# PSU.net
KiCad netlist of a schematic drawn in Altium Designer
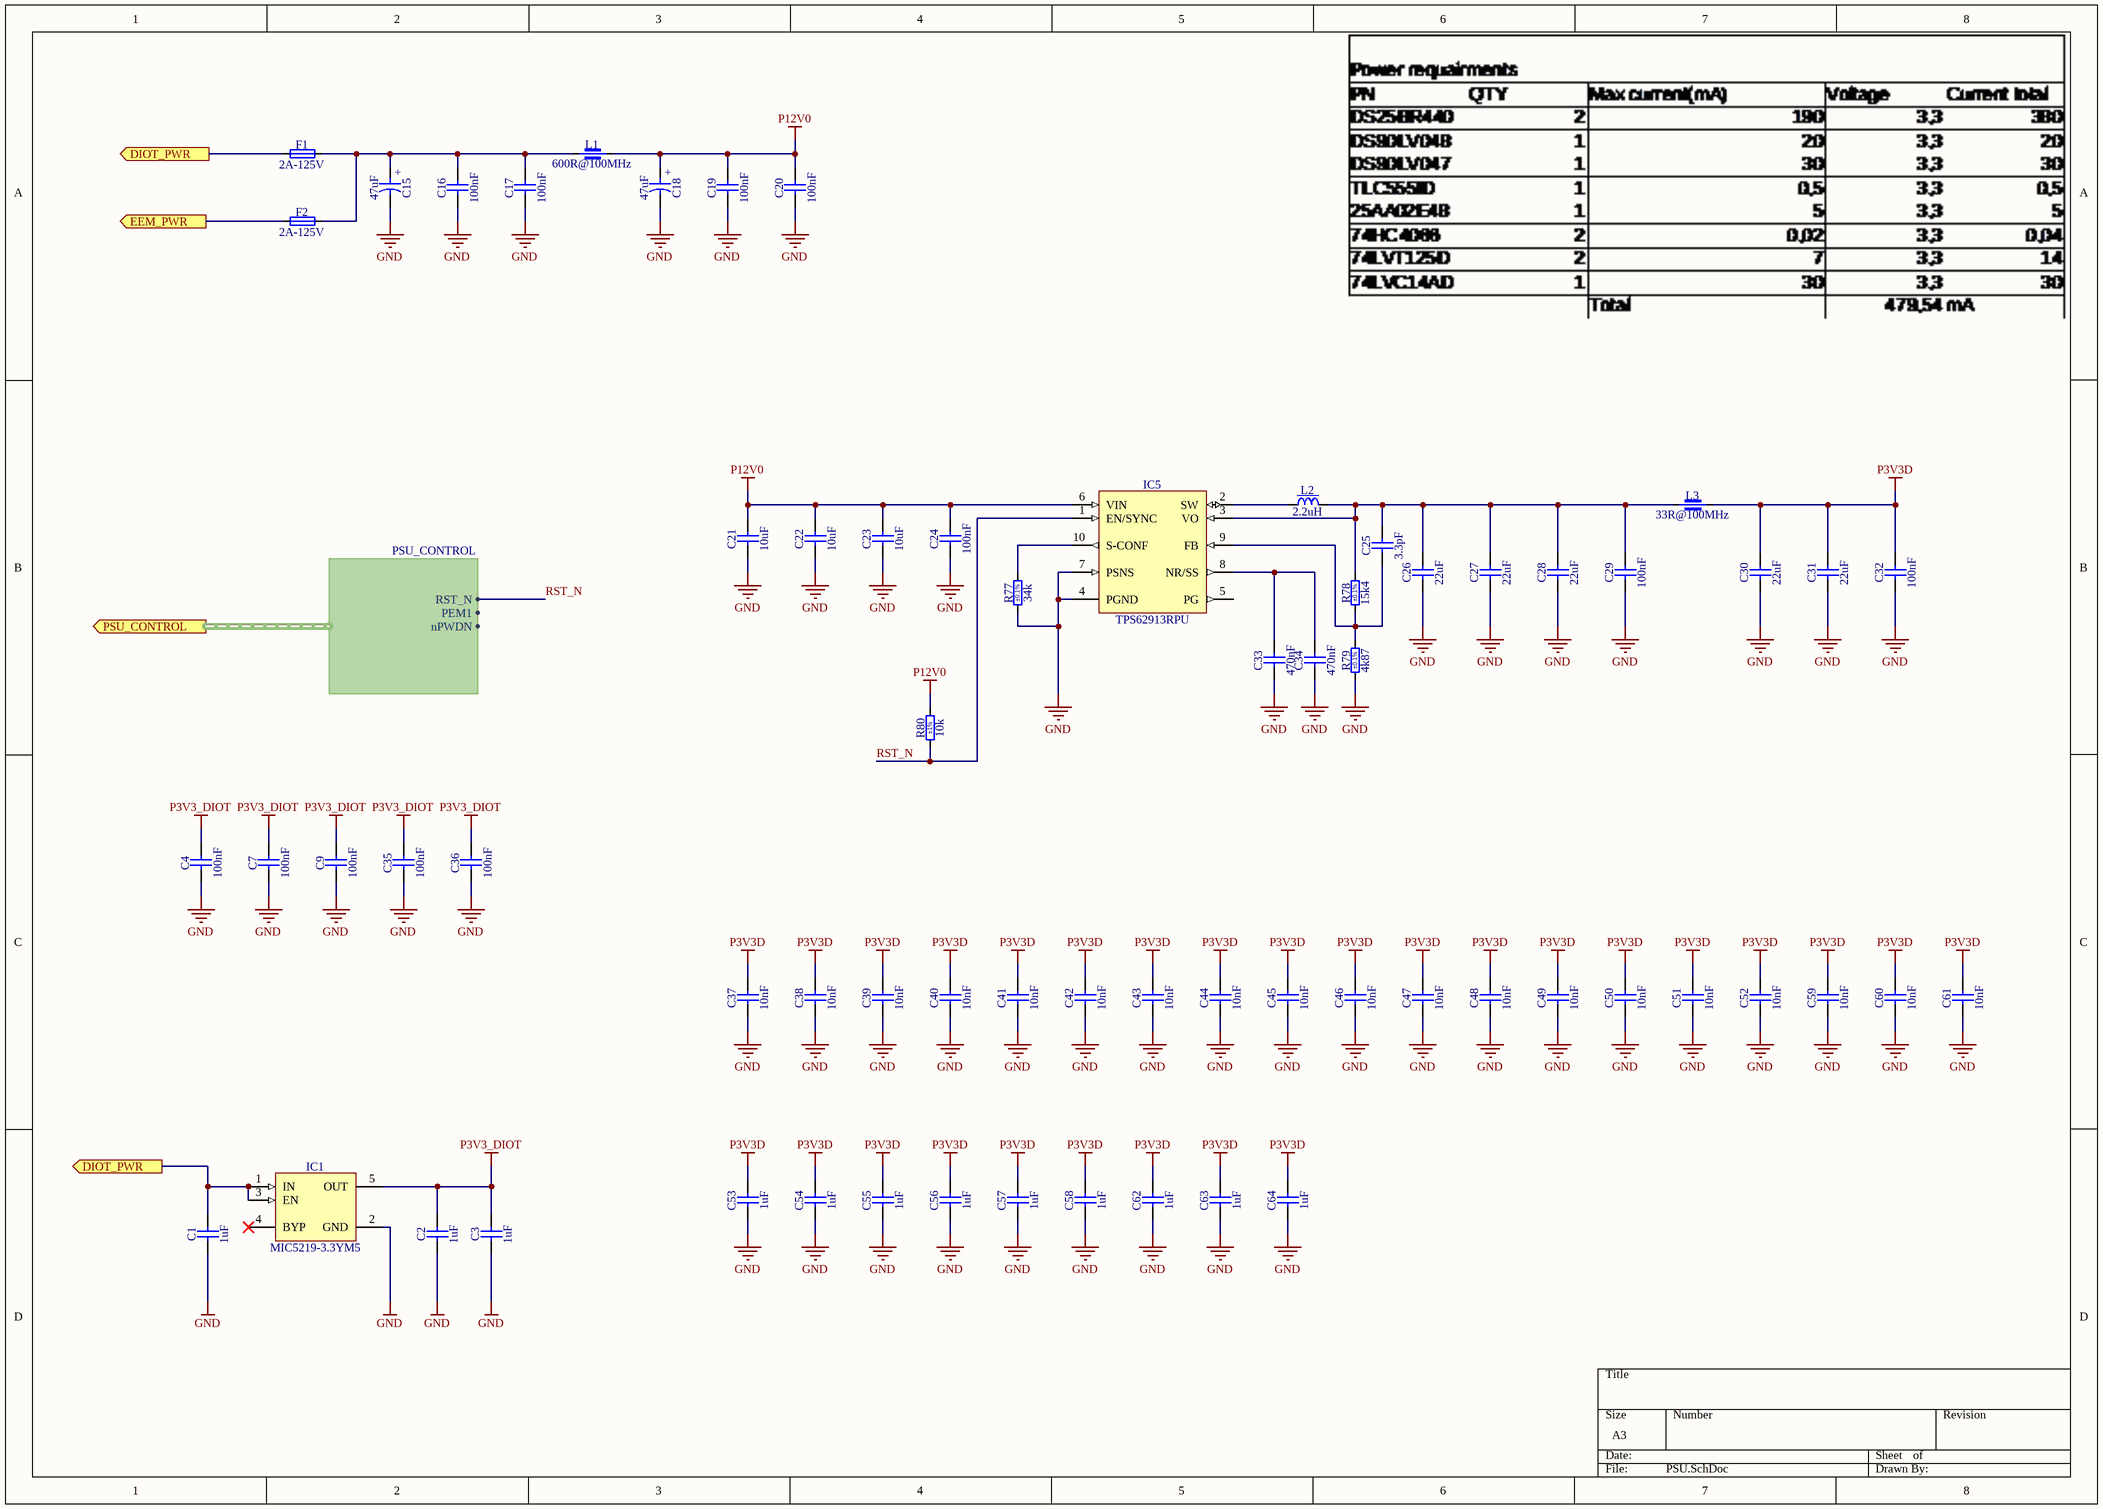
[diagram p0: PSU.SchDoc]

(export (version "E")
  (design (tool "Eeschema 10.0.6"))
  (components
    (comp (ref "C1")
      (value "1uF")
      (footprint "CAPC1608X87N")
      (description "Non-polarised capacitor")
      (fields
        (field (name "PART NUMBER") "CC0603_1UF_25V_10%_X7R")
        (field (name "VOLTAGE") "25V")
        (field (name "AUTHOR") "CERN DEM JLC")
      )
      (libsource (lib "Capacitors") (part "Capacitor - non polarized"))
    )
    (comp (ref "C2")
      (value "1uF")
      (footprint "CAPC1005X55N")
      (description "Non-polarised capacitor")
      (fields
        (field (name "PART NUMBER") "CC0402_1UF_16V_10%_X5R")
        (field (name "VOLTAGE") "16V")
        (field (name "AUTHOR") "CERN DEM JLC")
      )
      (libsource (lib "Capacitors") (part "Capacitor - non polarized"))
    )
    (comp (ref "C3")
      (value "1uF")
      (footprint "CAPC1005X55N")
      (description "Non-polarised capacitor")
      (fields
        (field (name "PART NUMBER") "CC0402_1UF_16V_10%_X5R")
        (field (name "VOLTAGE") "16V")
        (field (name "AUTHOR") "CERN DEM JLC")
      )
      (libsource (lib "Capacitors") (part "Capacitor - non polarized"))
    )
    (comp (ref "C4")
      (value "100nF")
      (footprint "CAPC1005X55N")
      (description "Non-polarised capacitor")
      (fields
        (field (name "PART NUMBER") "CC0402_100NF_16V_10%_X5R")
        (field (name "VOLTAGE") "16V")
        (field (name "AUTHOR") "CERN DEM JLC")
      )
      (libsource (lib "Capacitors") (part "Capacitor - non polarized"))
    )
    (comp (ref "C7")
      (value "100nF")
      (footprint "CAPC1005X55N")
      (description "Non-polarised capacitor")
      (fields
        (field (name "PART NUMBER") "CC0402_100NF_16V_10%_X5R")
        (field (name "VOLTAGE") "16V")
        (field (name "AUTHOR") "CERN DEM JLC")
      )
      (libsource (lib "Capacitors") (part "Capacitor - non polarized"))
    )
    (comp (ref "C9")
      (value "100nF")
      (footprint "CAPC1005X55N")
      (description "Non-polarised capacitor")
      (fields
        (field (name "PART NUMBER") "CC0402_100NF_16V_10%_X5R")
        (field (name "VOLTAGE") "16V")
        (field (name "AUTHOR") "CERN DEM JLC")
      )
      (libsource (lib "Capacitors") (part "Capacitor - non polarized"))
    )
    (comp (ref "C15")
      (value "47uF")
      (footprint "CAPMP7343X310N")
      (description "Polarised capacitor")
      (fields
        (field (name "PART NUMBER") "CTE7343-31_47UF_25V_10%")
        (field (name "VOLTAGE") "25V")
        (field (name "AUTHOR") "CERN DEM JLC")
      )
      (libsource (lib "Capacitors") (part "Capacitor - polarized"))
    )
    (comp (ref "C16")
      (value "100nF")
      (footprint "CAPC1608X90N")
      (description "Non-polarised capacitor")
      (fields
        (field (name "PART NUMBER") "CC0603_100NF_100V_10%_X7R")
        (field (name "VOLTAGE") "100V")
        (field (name "AUTHOR") "CERN DEM JLC")
      )
      (libsource (lib "Capacitors") (part "Capacitor - non polarized"))
    )
    (comp (ref "C17")
      (value "100nF")
      (footprint "CAPC1608X90N")
      (description "Non-polarised capacitor")
      (fields
        (field (name "PART NUMBER") "CC0603_100NF_100V_10%_X7R")
        (field (name "VOLTAGE") "100V")
        (field (name "AUTHOR") "CERN DEM JLC")
      )
      (libsource (lib "Capacitors") (part "Capacitor - non polarized"))
    )
    (comp (ref "C18")
      (value "47uF")
      (footprint "CAPMP7343X310N")
      (description "Polarised capacitor")
      (fields
        (field (name "PART NUMBER") "CTE7343-31_47UF_25V_10%")
        (field (name "VOLTAGE") "25V")
        (field (name "AUTHOR") "CERN DEM JLC")
      )
      (libsource (lib "Capacitors") (part "Capacitor - polarized"))
    )
    (comp (ref "C19")
      (value "100nF")
      (footprint "CAPC1608X90N")
      (description "Non-polarised capacitor")
      (fields
        (field (name "PART NUMBER") "CC0603_100NF_100V_10%_X7R")
        (field (name "VOLTAGE") "100V")
        (field (name "AUTHOR") "CERN DEM JLC")
      )
      (libsource (lib "Capacitors") (part "Capacitor - non polarized"))
    )
    (comp (ref "C20")
      (value "100nF")
      (footprint "CAPC1608X90N")
      (description "Non-polarised capacitor")
      (fields
        (field (name "PART NUMBER") "CC0603_100NF_100V_10%_X7R")
        (field (name "VOLTAGE") "100V")
        (field (name "AUTHOR") "CERN DEM JLC")
      )
      (libsource (lib "Capacitors") (part "Capacitor - non polarized"))
    )
    (comp (ref "C21")
      (value "10uF")
      (footprint "CAPC3216X180N")
      (description "Non-polarised capacitor")
      (fields
        (field (name "PART NUMBER") "CC1206_10UF_25V_10%_X7R")
        (field (name "VOLTAGE") "25V")
        (field (name "AUTHOR") "CERN DEM JLC")
      )
      (libsource (lib "Capacitors") (part "Capacitor - non polarized"))
    )
    (comp (ref "C22")
      (value "10uF")
      (footprint "CAPC3216X180N")
      (description "Non-polarised capacitor")
      (fields
        (field (name "PART NUMBER") "CC1206_10UF_25V_10%_X7R")
        (field (name "VOLTAGE") "25V")
        (field (name "AUTHOR") "CERN DEM JLC")
      )
      (libsource (lib "Capacitors") (part "Capacitor - non polarized"))
    )
    (comp (ref "C23")
      (value "10uF")
      (footprint "CAPC3216X180N")
      (description "Non-polarised capacitor")
      (fields
        (field (name "PART NUMBER") "CC1206_10UF_25V_10%_X7R")
        (field (name "VOLTAGE") "25V")
        (field (name "AUTHOR") "CERN DEM JLC")
      )
      (libsource (lib "Capacitors") (part "Capacitor - non polarized"))
    )
    (comp (ref "C24")
      (value "100nF")
      (footprint "CAPC2012X135N")
      (description "Non-polarised capacitor")
      (fields
        (field (name "PART NUMBER") "CC0805_100NF_50V_10%_X7R")
        (field (name "VOLTAGE") "50V")
        (field (name "AUTHOR") "CERN DEM JLC")
      )
      (libsource (lib "Capacitors") (part "Capacitor - non polarized"))
    )
    (comp (ref "C25")
      (value "3.3pF")
      (footprint "CAPC1608X87N")
      (description "Non-polarised capacitor")
      (fields
        (field (name "PART NUMBER") "CC0603_3.3PF_50V_0.25PF_NP0")
        (field (name "VOLTAGE") "50V")
        (field (name "AUTHOR") "CERN DEM JLC")
      )
      (libsource (lib "Capacitors") (part "Capacitor - non polarized"))
    )
    (comp (ref "C26")
      (value "22uF")
      (footprint "CAPC3216X180N")
      (description "Non-polarised capacitor")
      (fields
        (field (name "PART NUMBER") "CC1206_22UF_10V_10%_X7R")
        (field (name "VOLTAGE") "10V")
        (field (name "AUTHOR") "CERN DEM JLC")
      )
      (libsource (lib "Capacitors") (part "Capacitor - non polarized"))
    )
    (comp (ref "C27")
      (value "22uF")
      (footprint "CAPC3216X180N")
      (description "Non-polarised capacitor")
      (fields
        (field (name "PART NUMBER") "CC1206_22UF_10V_10%_X7R")
        (field (name "VOLTAGE") "10V")
        (field (name "AUTHOR") "CERN DEM JLC")
      )
      (libsource (lib "Capacitors") (part "Capacitor - non polarized"))
    )
    (comp (ref "C28")
      (value "22uF")
      (footprint "CAPC3216X180N")
      (description "Non-polarised capacitor")
      (fields
        (field (name "PART NUMBER") "CC1206_22UF_10V_10%_X7R")
        (field (name "VOLTAGE") "10V")
        (field (name "AUTHOR") "CERN DEM JLC")
      )
      (libsource (lib "Capacitors") (part "Capacitor - non polarized"))
    )
    (comp (ref "C29")
      (value "100nF")
      (footprint "CAPC3216X180N")
      (description "Non-polarised capacitor")
      (fields
        (field (name "PART NUMBER") "CC1206_100NF_50V_5%_C0G_TDK_CGA5L2C0G1H104J160AA")
        (field (name "VOLTAGE") "50V")
        (field (name "AUTHOR") "CERN DEM BC")
      )
      (libsource (lib "Capacitors") (part "Capacitor - non polarized"))
    )
    (comp (ref "C30")
      (value "22uF")
      (footprint "CAPC3216X180N")
      (description "Non-polarised capacitor")
      (fields
        (field (name "PART NUMBER") "CC1206_22UF_10V_10%_X7R")
        (field (name "VOLTAGE") "10V")
        (field (name "AUTHOR") "CERN DEM JLC")
      )
      (libsource (lib "Capacitors") (part "Capacitor - non polarized"))
    )
    (comp (ref "C31")
      (value "22uF")
      (footprint "CAPC3216X180N")
      (description "Non-polarised capacitor")
      (fields
        (field (name "PART NUMBER") "CC1206_22UF_10V_10%_X7R")
        (field (name "VOLTAGE") "10V")
        (field (name "AUTHOR") "CERN DEM JLC")
      )
      (libsource (lib "Capacitors") (part "Capacitor - non polarized"))
    )
    (comp (ref "C32")
      (value "100nF")
      (footprint "CAPC3216X180N")
      (description "Non-polarised capacitor")
      (fields
        (field (name "PART NUMBER") "CC1206_100NF_50V_5%_C0G_TDK_CGA5L2C0G1H104J160AA")
        (field (name "VOLTAGE") "50V")
        (field (name "AUTHOR") "CERN DEM BC")
      )
      (libsource (lib "Capacitors") (part "Capacitor - non polarized"))
    )
    (comp (ref "C33")
      (value "470nF")
      (footprint "CAPC1608X90N")
      (description "Non-polarised capacitor")
      (fields
        (field (name "PART NUMBER") "CC0603_470NF_16V_10%_X7R")
        (field (name "VOLTAGE") "16V")
        (field (name "AUTHOR") "CERN DEM BC")
      )
      (libsource (lib "Capacitors") (part "Capacitor - non polarized"))
    )
    (comp (ref "C34")
      (value "470nF")
      (footprint "CAPC1608X90N")
      (description "Non-polarised capacitor")
      (fields
        (field (name "PART NUMBER") "CC0603_470NF_16V_10%_X7R")
        (field (name "VOLTAGE") "16V")
        (field (name "AUTHOR") "CERN DEM BC")
      )
      (libsource (lib "Capacitors") (part "Capacitor - non polarized"))
    )
    (comp (ref "C35")
      (value "100nF")
      (footprint "CAPC1005X55N")
      (description "Non-polarised capacitor")
      (fields
        (field (name "PART NUMBER") "CC0402_100NF_16V_10%_X5R")
        (field (name "VOLTAGE") "16V")
        (field (name "AUTHOR") "CERN DEM JLC")
      )
      (libsource (lib "Capacitors") (part "Capacitor - non polarized"))
    )
    (comp (ref "C36")
      (value "100nF")
      (footprint "CAPC1005X55N")
      (description "Non-polarised capacitor")
      (fields
        (field (name "PART NUMBER") "CC0402_100NF_16V_10%_X5R")
        (field (name "VOLTAGE") "16V")
        (field (name "AUTHOR") "CERN DEM JLC")
      )
      (libsource (lib "Capacitors") (part "Capacitor - non polarized"))
    )
    (comp (ref "C37")
      (value "10nF")
      (footprint "CAPC1005X55N")
      (description "Non-polarised capacitor")
      (fields
        (field (name "PART NUMBER") "CC0402_10NF_16V_10%_X7R")
        (field (name "VOLTAGE") "16V")
        (field (name "AUTHOR") "CERN DEM JLC")
      )
      (libsource (lib "Capacitors") (part "Capacitor - non polarized"))
    )
    (comp (ref "C38")
      (value "10nF")
      (footprint "CAPC1005X55N")
      (description "Non-polarised capacitor")
      (fields
        (field (name "PART NUMBER") "CC0402_10NF_16V_10%_X7R")
        (field (name "VOLTAGE") "16V")
        (field (name "AUTHOR") "CERN DEM JLC")
      )
      (libsource (lib "Capacitors") (part "Capacitor - non polarized"))
    )
    (comp (ref "C39")
      (value "10nF")
      (footprint "CAPC1005X55N")
      (description "Non-polarised capacitor")
      (fields
        (field (name "PART NUMBER") "CC0402_10NF_16V_10%_X7R")
        (field (name "VOLTAGE") "16V")
        (field (name "AUTHOR") "CERN DEM JLC")
      )
      (libsource (lib "Capacitors") (part "Capacitor - non polarized"))
    )
    (comp (ref "C40")
      (value "10nF")
      (footprint "CAPC1005X55N")
      (description "Non-polarised capacitor")
      (fields
        (field (name "PART NUMBER") "CC0402_10NF_16V_10%_X7R")
        (field (name "VOLTAGE") "16V")
        (field (name "AUTHOR") "CERN DEM JLC")
      )
      (libsource (lib "Capacitors") (part "Capacitor - non polarized"))
    )
    (comp (ref "C41")
      (value "10nF")
      (footprint "CAPC1005X55N")
      (description "Non-polarised capacitor")
      (fields
        (field (name "PART NUMBER") "CC0402_10NF_16V_10%_X7R")
        (field (name "VOLTAGE") "16V")
        (field (name "AUTHOR") "CERN DEM JLC")
      )
      (libsource (lib "Capacitors") (part "Capacitor - non polarized"))
    )
    (comp (ref "C42")
      (value "10nF")
      (footprint "CAPC1005X55N")
      (description "Non-polarised capacitor")
      (fields
        (field (name "PART NUMBER") "CC0402_10NF_16V_10%_X7R")
        (field (name "VOLTAGE") "16V")
        (field (name "AUTHOR") "CERN DEM JLC")
      )
      (libsource (lib "Capacitors") (part "Capacitor - non polarized"))
    )
    (comp (ref "C43")
      (value "10nF")
      (footprint "CAPC1005X55N")
      (description "Non-polarised capacitor")
      (fields
        (field (name "PART NUMBER") "CC0402_10NF_16V_10%_X7R")
        (field (name "VOLTAGE") "16V")
        (field (name "AUTHOR") "CERN DEM JLC")
      )
      (libsource (lib "Capacitors") (part "Capacitor - non polarized"))
    )
    (comp (ref "C44")
      (value "10nF")
      (footprint "CAPC1005X55N")
      (description "Non-polarised capacitor")
      (fields
        (field (name "PART NUMBER") "CC0402_10NF_16V_10%_X7R")
        (field (name "VOLTAGE") "16V")
        (field (name "AUTHOR") "CERN DEM JLC")
      )
      (libsource (lib "Capacitors") (part "Capacitor - non polarized"))
    )
    (comp (ref "C45")
      (value "10nF")
      (footprint "CAPC1005X55N")
      (description "Non-polarised capacitor")
      (fields
        (field (name "PART NUMBER") "CC0402_10NF_16V_10%_X7R")
        (field (name "VOLTAGE") "16V")
        (field (name "AUTHOR") "CERN DEM JLC")
      )
      (libsource (lib "Capacitors") (part "Capacitor - non polarized"))
    )
    (comp (ref "C46")
      (value "10nF")
      (footprint "CAPC1005X55N")
      (description "Non-polarised capacitor")
      (fields
        (field (name "PART NUMBER") "CC0402_10NF_16V_10%_X7R")
        (field (name "VOLTAGE") "16V")
        (field (name "AUTHOR") "CERN DEM JLC")
      )
      (libsource (lib "Capacitors") (part "Capacitor - non polarized"))
    )
    (comp (ref "C47")
      (value "10nF")
      (footprint "CAPC1005X55N")
      (description "Non-polarised capacitor")
      (fields
        (field (name "PART NUMBER") "CC0402_10NF_16V_10%_X7R")
        (field (name "VOLTAGE") "16V")
        (field (name "AUTHOR") "CERN DEM JLC")
      )
      (libsource (lib "Capacitors") (part "Capacitor - non polarized"))
    )
    (comp (ref "C48")
      (value "10nF")
      (footprint "CAPC1005X55N")
      (description "Non-polarised capacitor")
      (fields
        (field (name "PART NUMBER") "CC0402_10NF_16V_10%_X7R")
        (field (name "VOLTAGE") "16V")
        (field (name "AUTHOR") "CERN DEM JLC")
      )
      (libsource (lib "Capacitors") (part "Capacitor - non polarized"))
    )
    (comp (ref "C49")
      (value "10nF")
      (footprint "CAPC1005X55N")
      (description "Non-polarised capacitor")
      (fields
        (field (name "PART NUMBER") "CC0402_10NF_16V_10%_X7R")
        (field (name "VOLTAGE") "16V")
        (field (name "AUTHOR") "CERN DEM JLC")
      )
      (libsource (lib "Capacitors") (part "Capacitor - non polarized"))
    )
    (comp (ref "C50")
      (value "10nF")
      (footprint "CAPC1005X55N")
      (description "Non-polarised capacitor")
      (fields
        (field (name "PART NUMBER") "CC0402_10NF_16V_10%_X7R")
        (field (name "VOLTAGE") "16V")
        (field (name "AUTHOR") "CERN DEM JLC")
      )
      (libsource (lib "Capacitors") (part "Capacitor - non polarized"))
    )
    (comp (ref "C51")
      (value "10nF")
      (footprint "CAPC1005X55N")
      (description "Non-polarised capacitor")
      (fields
        (field (name "PART NUMBER") "CC0402_10NF_16V_10%_X7R")
        (field (name "VOLTAGE") "16V")
        (field (name "AUTHOR") "CERN DEM JLC")
      )
      (libsource (lib "Capacitors") (part "Capacitor - non polarized"))
    )
    (comp (ref "C52")
      (value "10nF")
      (footprint "CAPC1005X55N")
      (description "Non-polarised capacitor")
      (fields
        (field (name "PART NUMBER") "CC0402_10NF_16V_10%_X7R")
        (field (name "VOLTAGE") "16V")
        (field (name "AUTHOR") "CERN DEM JLC")
      )
      (libsource (lib "Capacitors") (part "Capacitor - non polarized"))
    )
    (comp (ref "C53")
      (value "1uF")
      (footprint "CAPC2012X135N")
      (description "Non-polarised capacitor")
      (fields
        (field (name "PART NUMBER") "CC0805_1UF_16V_10%_X7R")
        (field (name "VOLTAGE") "16V")
        (field (name "AUTHOR") "CERN DEM JLC")
      )
      (libsource (lib "Capacitors") (part "Capacitor - non polarized"))
    )
    (comp (ref "C54")
      (value "1uF")
      (footprint "CAPC2012X135N")
      (description "Non-polarised capacitor")
      (fields
        (field (name "PART NUMBER") "CC0805_1UF_16V_10%_X7R")
        (field (name "VOLTAGE") "16V")
        (field (name "AUTHOR") "CERN DEM JLC")
      )
      (libsource (lib "Capacitors") (part "Capacitor - non polarized"))
    )
    (comp (ref "C55")
      (value "1uF")
      (footprint "CAPC2012X135N")
      (description "Non-polarised capacitor")
      (fields
        (field (name "PART NUMBER") "CC0805_1UF_16V_10%_X7R")
        (field (name "VOLTAGE") "16V")
        (field (name "AUTHOR") "CERN DEM JLC")
      )
      (libsource (lib "Capacitors") (part "Capacitor - non polarized"))
    )
    (comp (ref "C56")
      (value "1uF")
      (footprint "CAPC2012X135N")
      (description "Non-polarised capacitor")
      (fields
        (field (name "PART NUMBER") "CC0805_1UF_16V_10%_X7R")
        (field (name "VOLTAGE") "16V")
        (field (name "AUTHOR") "CERN DEM JLC")
      )
      (libsource (lib "Capacitors") (part "Capacitor - non polarized"))
    )
    (comp (ref "C57")
      (value "1uF")
      (footprint "CAPC2012X135N")
      (description "Non-polarised capacitor")
      (fields
        (field (name "PART NUMBER") "CC0805_1UF_16V_10%_X7R")
        (field (name "VOLTAGE") "16V")
        (field (name "AUTHOR") "CERN DEM JLC")
      )
      (libsource (lib "Capacitors") (part "Capacitor - non polarized"))
    )
    (comp (ref "C58")
      (value "1uF")
      (footprint "CAPC2012X135N")
      (description "Non-polarised capacitor")
      (fields
        (field (name "PART NUMBER") "CC0805_1UF_16V_10%_X7R")
        (field (name "VOLTAGE") "16V")
        (field (name "AUTHOR") "CERN DEM JLC")
      )
      (libsource (lib "Capacitors") (part "Capacitor - non polarized"))
    )
    (comp (ref "C59")
      (value "10nF")
      (footprint "CAPC1005X55N")
      (description "Non-polarised capacitor")
      (fields
        (field (name "PART NUMBER") "CC0402_10NF_16V_10%_X7R")
        (field (name "VOLTAGE") "16V")
        (field (name "AUTHOR") "CERN DEM JLC")
      )
      (libsource (lib "Capacitors") (part "Capacitor - non polarized"))
    )
    (comp (ref "C60")
      (value "10nF")
      (footprint "CAPC1005X55N")
      (description "Non-polarised capacitor")
      (fields
        (field (name "PART NUMBER") "CC0402_10NF_16V_10%_X7R")
        (field (name "VOLTAGE") "16V")
        (field (name "AUTHOR") "CERN DEM JLC")
      )
      (libsource (lib "Capacitors") (part "Capacitor - non polarized"))
    )
    (comp (ref "C61")
      (value "10nF")
      (footprint "CAPC1005X55N")
      (description "Non-polarised capacitor")
      (fields
        (field (name "PART NUMBER") "CC0402_10NF_16V_10%_X7R")
        (field (name "VOLTAGE") "16V")
        (field (name "AUTHOR") "CERN DEM JLC")
      )
      (libsource (lib "Capacitors") (part "Capacitor - non polarized"))
    )
    (comp (ref "C62")
      (value "1uF")
      (footprint "CAPC2012X135N")
      (description "Non-polarised capacitor")
      (fields
        (field (name "PART NUMBER") "CC0805_1UF_16V_10%_X7R")
        (field (name "VOLTAGE") "16V")
        (field (name "AUTHOR") "CERN DEM JLC")
      )
      (libsource (lib "Capacitors") (part "Capacitor - non polarized"))
    )
    (comp (ref "C63")
      (value "1uF")
      (footprint "CAPC2012X135N")
      (description "Non-polarised capacitor")
      (fields
        (field (name "PART NUMBER") "CC0805_1UF_16V_10%_X7R")
        (field (name "VOLTAGE") "16V")
        (field (name "AUTHOR") "CERN DEM JLC")
      )
      (libsource (lib "Capacitors") (part "Capacitor - non polarized"))
    )
    (comp (ref "C64")
      (value "1uF")
      (footprint "CAPC2012X135N")
      (description "Non-polarised capacitor")
      (fields
        (field (name "PART NUMBER") "CC0805_1UF_16V_10%_X7R")
        (field (name "VOLTAGE") "16V")
        (field (name "AUTHOR") "CERN DEM JLC")
      )
      (libsource (lib "Capacitors") (part "Capacitor - non polarized"))
    )
    (comp (ref "F1")
      (value "2A-125V")
      (footprint "FUSE_LITTELFUSE_0154")
      (description "Fuse")
      (fields
        (field (name "PART NUMBER") "FUSE_LITTELFUSE_0154002.DR")
        (field (name "MANUFACTURER") "LITTELFUSE")
        (field (name "AUTHOR") "CERN DEM JMW")
      )
      (libsource (lib "Eletro-mechanical") (part "Fuse"))
    )
    (comp (ref "F2")
      (value "2A-125V")
      (footprint "FUSE_LITTELFUSE_0154")
      (description "Fuse")
      (fields
        (field (name "PART NUMBER") "FUSE_LITTELFUSE_0154002.DR")
        (field (name "MANUFACTURER") "LITTELFUSE")
        (field (name "AUTHOR") "CERN DEM JMW")
      )
      (libsource (lib "Eletro-mechanical") (part "Fuse"))
    )
    (comp (ref "IC1")
      (value "MIC5219-3.3YM5")
      (footprint "SOT95P280X145-5N")
      (description "500mA Peak Output LDO Regulator")
      (fields (field (name "MANUFACTURER") "MICROCHIP TECHNOLOGY") (field (name "AUTHOR") "CERN DEM WB"))
      (libsource (lib "ICs And Semiconductors") (part "MIC5219-X.XYM5"))
    )
    (comp (ref "IC5")
      (value "TPS62913RPU")
      (footprint "TEXAS_RPU0010A")
      (fields (field (name "MANUFACTURER") "TEXAS INSTRUMENTS") (field (name "AUTHOR") "CERN DEM BC"))
      (libsource (lib "ICs And Semiconductors") (part "TPS6291x"))
    )
    (comp (ref "L1")
      (value "600R@100MHz")
      (footprint "INDC2012X110N")
      (fields
        (field (name "PART NUMBER") "IND0805_WURTH_742792040")
        (field (name "POWER") "2A")
        (field (name "TOLERANCE") "±25%")
        (field (name "AUTHOR") "CERN DEM JLC")
      )
      (libsource (lib "Inductors & Transformers") (part "Ferrite Bead"))
    )
    (comp (ref "L2")
      (value "2.2uH")
      (footprint "IND_WURTH_WE-MAPI_4020")
      (description "Inductor With Core")
      (fields
        (field (name "PART NUMBER") "IND_2.2UH_20%_WURTH_WE-MAPI-74438356022")
        (field (name "POWER") "4.7A")
        (field (name "AUTHOR") "CERN DEM HF")
      )
      (libsource (lib "Inductors & Transformers") (part "Inductor With Magnetic core"))
    )
    (comp (ref "L3")
      (value "33R@100MHz")
      (footprint "IND_KEMET_Z0805PWS")
      (fields
        (field (name "PART NUMBER") "IND0805_KEMET_Z0805C330BPWS")
        (field (name "POWER") "4A")
        (field (name "TOLERANCE") "±25%")
        (field (name "AUTHOR") "CERN DEM JMW")
      )
      (libsource (lib "Inductors & Transformers") (part "Ferrite Bead"))
    )
    (comp (ref "R77")
      (value "34k")
      (footprint "RESC1608X55N")
      (description "Resistor - 0.1%")
      (fields
        (field (name "TOLERANCE") "±0.1%")
        (field (name "PART NUMBER") "R0603_34K_0.1%_0.063W_10PPM")
        (field (name "POWER") "0.063W")
        (field (name "AUTHOR") "CERN DEM JLC")
      )
      (libsource (lib "Resistors") (part "Resistor - 0.1%"))
    )
    (comp (ref "R78")
      (value "15k4")
      (footprint "RESC1608X55N")
      (description "Resistor - 0.1%")
      (fields
        (field (name "TOLERANCE") "±0.1%")
        (field (name "PART NUMBER") "R0603_15K4_0.1%_0.063W_10PPM")
        (field (name "POWER") "0.063W")
        (field (name "AUTHOR") "CERN DEM JLC")
      )
      (libsource (lib "Resistors") (part "Resistor - 0.1%"))
    )
    (comp (ref "R79")
      (value "4k87")
      (footprint "RESC1608X55N")
      (description "Resistor - 0.1%")
      (fields
        (field (name "TOLERANCE") "±0.1%")
        (field (name "PART NUMBER") "R0603_4K87_0.1%_0.063W_10PPM")
        (field (name "POWER") "0.063W")
        (field (name "AUTHOR") "CERN DEM JLC")
      )
      (libsource (lib "Resistors") (part "Resistor - 0.1%"))
    )
    (comp (ref "R80")
      (value "10k")
      (footprint "RESC1608X55N")
      (description "Resistor - 1%")
      (fields
        (field (name "TOLERANCE") "±1%")
        (field (name "PART NUMBER") "R0603_10K_1%_0.1W_100PPM")
        (field (name "POWER") "0.1W")
        (field (name "AUTHOR") "CERN DEM JLC")
      )
      (libsource (lib "Resistors") (part "Resistor - 1%"))
    )
  )
  (nets
    (net (code "2") (name "/DIOT_PWR") (class "Default")
      (node (ref "C1") (pin "2") (pinfunction "2_2") (pintype "passive"))
      (node (ref "F1") (pin "1") (pinfunction "1_1") (pintype "passive"))
      (node (ref "IC1") (pin "1") (pinfunction "IN_1") (pintype "input"))
      (node (ref "IC1") (pin "3") (pinfunction "EN_3") (pintype "input"))
    )
    (net (code "3") (name "/EEM_PWR") (class "Default")
      (node (ref "F2") (pin "1") (pinfunction "1_1") (pintype "passive"))
    )
    (net (code "4") (name "/RST_N") (class "Default")
      (node (ref "IC5") (pin "1") (pinfunction "EN/SYNC_1") (pintype "input"))
      (node (ref "R80") (pin "1") (pinfunction "1_1") (pintype "passive"))
    )
    (net (code "6") (name "GND") (class "Default")
      (node (ref "C1") (pin "1") (pinfunction "1_1") (pintype "passive"))
      (node (ref "C15") (pin "2") (pinfunction "2_2") (pintype "passive"))
      (node (ref "C16") (pin "1") (pinfunction "1_1") (pintype "passive"))
      (node (ref "C17") (pin "1") (pinfunction "1_1") (pintype "passive"))
      (node (ref "C18") (pin "2") (pinfunction "2_2") (pintype "passive"))
      (node (ref "C19") (pin "1") (pinfunction "1_1") (pintype "passive"))
      (node (ref "C2") (pin "1") (pinfunction "1_1") (pintype "passive"))
      (node (ref "C20") (pin "1") (pinfunction "1_1") (pintype "passive"))
      (node (ref "C21") (pin "1") (pinfunction "1_1") (pintype "passive"))
      (node (ref "C22") (pin "1") (pinfunction "1_1") (pintype "passive"))
      (node (ref "C23") (pin "1") (pinfunction "1_1") (pintype "passive"))
      (node (ref "C24") (pin "1") (pinfunction "1_1") (pintype "passive"))
      (node (ref "C26") (pin "1") (pinfunction "1_1") (pintype "passive"))
      (node (ref "C27") (pin "1") (pinfunction "1_1") (pintype "passive"))
      (node (ref "C28") (pin "1") (pinfunction "1_1") (pintype "passive"))
      (node (ref "C29") (pin "1") (pinfunction "1_1") (pintype "passive"))
      (node (ref "C3") (pin "1") (pinfunction "1_1") (pintype "passive"))
      (node (ref "C30") (pin "1") (pinfunction "1_1") (pintype "passive"))
      (node (ref "C31") (pin "1") (pinfunction "1_1") (pintype "passive"))
      (node (ref "C32") (pin "1") (pinfunction "1_1") (pintype "passive"))
      (node (ref "C33") (pin "1") (pinfunction "1_1") (pintype "passive"))
      (node (ref "C34") (pin "1") (pinfunction "1_1") (pintype "passive"))
      (node (ref "C35") (pin "1") (pinfunction "1_1") (pintype "passive"))
      (node (ref "C36") (pin "1") (pinfunction "1_1") (pintype "passive"))
      (node (ref "C37") (pin "1") (pinfunction "1_1") (pintype "passive"))
      (node (ref "C38") (pin "1") (pinfunction "1_1") (pintype "passive"))
      (node (ref "C39") (pin "1") (pinfunction "1_1") (pintype "passive"))
      (node (ref "C4") (pin "1") (pinfunction "1_1") (pintype "passive"))
      (node (ref "C40") (pin "1") (pinfunction "1_1") (pintype "passive"))
      (node (ref "C41") (pin "1") (pinfunction "1_1") (pintype "passive"))
      (node (ref "C42") (pin "1") (pinfunction "1_1") (pintype "passive"))
      (node (ref "C43") (pin "1") (pinfunction "1_1") (pintype "passive"))
      (node (ref "C44") (pin "1") (pinfunction "1_1") (pintype "passive"))
      (node (ref "C45") (pin "1") (pinfunction "1_1") (pintype "passive"))
      (node (ref "C46") (pin "1") (pinfunction "1_1") (pintype "passive"))
      (node (ref "C47") (pin "1") (pinfunction "1_1") (pintype "passive"))
      (node (ref "C48") (pin "1") (pinfunction "1_1") (pintype "passive"))
      (node (ref "C49") (pin "1") (pinfunction "1_1") (pintype "passive"))
      (node (ref "C50") (pin "1") (pinfunction "1_1") (pintype "passive"))
      (node (ref "C51") (pin "1") (pinfunction "1_1") (pintype "passive"))
      (node (ref "C52") (pin "1") (pinfunction "1_1") (pintype "passive"))
      (node (ref "C53") (pin "1") (pinfunction "1_1") (pintype "passive"))
      (node (ref "C54") (pin "1") (pinfunction "1_1") (pintype "passive"))
      (node (ref "C55") (pin "1") (pinfunction "1_1") (pintype "passive"))
      (node (ref "C56") (pin "1") (pinfunction "1_1") (pintype "passive"))
      (node (ref "C57") (pin "1") (pinfunction "1_1") (pintype "passive"))
      (node (ref "C58") (pin "1") (pinfunction "1_1") (pintype "passive"))
      (node (ref "C59") (pin "1") (pinfunction "1_1") (pintype "passive"))
      (node (ref "C60") (pin "1") (pinfunction "1_1") (pintype "passive"))
      (node (ref "C61") (pin "1") (pinfunction "1_1") (pintype "passive"))
      (node (ref "C62") (pin "1") (pinfunction "1_1") (pintype "passive"))
      (node (ref "C63") (pin "1") (pinfunction "1_1") (pintype "passive"))
      (node (ref "C64") (pin "1") (pinfunction "1_1") (pintype "passive"))
      (node (ref "C7") (pin "1") (pinfunction "1_1") (pintype "passive"))
      (node (ref "C9") (pin "1") (pinfunction "1_1") (pintype "passive"))
      (node (ref "IC1") (pin "2") (pinfunction "GND_2") (pintype "power_in"))
      (node (ref "IC5") (pin "4") (pinfunction "PGND_4") (pintype "power_in"))
      (node (ref "IC5") (pin "7") (pinfunction "PSNS_7") (pintype "input"))
      (node (ref "R77") (pin "1") (pinfunction "1_1") (pintype "passive"))
      (node (ref "R79") (pin "1") (pinfunction "1_1") (pintype "passive"))
    )
    (net (code "7") (name "Net-(C15-Pad1)") (class "Default")
      (node (ref "C15") (pin "1") (pinfunction "1_1") (pintype "passive"))
      (node (ref "C16") (pin "2") (pinfunction "2_2") (pintype "passive"))
      (node (ref "C17") (pin "2") (pinfunction "2_2") (pintype "passive"))
      (node (ref "F1") (pin "2") (pinfunction "2_2") (pintype "passive"))
      (node (ref "F2") (pin "2") (pinfunction "2_2") (pintype "passive"))
      (node (ref "L1") (pin "1") (pinfunction "1_1") (pintype "passive"))
    )
    (net (code "8") (name "Net-(IC5-FB)") (class "Default")
      (node (ref "C25") (pin "1") (pinfunction "1_1") (pintype "passive"))
      (node (ref "IC5") (pin "9") (pinfunction "FB_9") (pintype "input"))
      (node (ref "R78") (pin "1") (pinfunction "1_1") (pintype "passive"))
      (node (ref "R79") (pin "2") (pinfunction "2_2") (pintype "passive"))
    )
    (net (code "9") (name "Net-(IC5-NR{slash}SS)") (class "Default")
      (node (ref "C33") (pin "2") (pinfunction "2_2") (pintype "passive"))
      (node (ref "C34") (pin "2") (pinfunction "2_2") (pintype "passive"))
      (node (ref "IC5") (pin "8") (pinfunction "NR/SS_8") (pintype "output"))
    )
    (net (code "10") (name "Net-(IC5-S-CONF)") (class "Default")
      (node (ref "IC5") (pin "10") (pinfunction "S-CONF_10") (pintype "output"))
      (node (ref "R77") (pin "2") (pinfunction "2_2") (pintype "passive"))
    )
    (net (code "11") (name "Net-(IC5-SW)") (class "Default")
      (node (ref "IC5") (pin "2") (pinfunction "SW_2") (pintype "bidirectional"))
      (node (ref "L2") (pin "1") (pinfunction "1_1") (pintype "passive"))
    )
    (net (code "12") (name "Net-(IC5-VO)") (class "Default")
      (node (ref "C25") (pin "2") (pinfunction "2_2") (pintype "passive"))
      (node (ref "C26") (pin "2") (pinfunction "2_2") (pintype "passive"))
      (node (ref "C27") (pin "2") (pinfunction "2_2") (pintype "passive"))
      (node (ref "C28") (pin "2") (pinfunction "2_2") (pintype "passive"))
      (node (ref "C29") (pin "2") (pinfunction "2_2") (pintype "passive"))
      (node (ref "IC5") (pin "3") (pinfunction "VO_3") (pintype "input"))
      (node (ref "L2") (pin "2") (pinfunction "2_2") (pintype "passive"))
      (node (ref "L3") (pin "1") (pinfunction "1_1") (pintype "passive"))
      (node (ref "R78") (pin "2") (pinfunction "2_2") (pintype "passive"))
    )
    (net (code "13") (name "P3V3D") (class "Default")
      (node (ref "C30") (pin "2") (pinfunction "2_2") (pintype "passive"))
      (node (ref "C31") (pin "2") (pinfunction "2_2") (pintype "passive"))
      (node (ref "C32") (pin "2") (pinfunction "2_2") (pintype "passive"))
      (node (ref "C37") (pin "2") (pinfunction "2_2") (pintype "passive"))
      (node (ref "C38") (pin "2") (pinfunction "2_2") (pintype "passive"))
      (node (ref "C39") (pin "2") (pinfunction "2_2") (pintype "passive"))
      (node (ref "C40") (pin "2") (pinfunction "2_2") (pintype "passive"))
      (node (ref "C41") (pin "2") (pinfunction "2_2") (pintype "passive"))
      (node (ref "C42") (pin "2") (pinfunction "2_2") (pintype "passive"))
      (node (ref "C43") (pin "2") (pinfunction "2_2") (pintype "passive"))
      (node (ref "C44") (pin "2") (pinfunction "2_2") (pintype "passive"))
      (node (ref "C45") (pin "2") (pinfunction "2_2") (pintype "passive"))
      (node (ref "C46") (pin "2") (pinfunction "2_2") (pintype "passive"))
      (node (ref "C47") (pin "2") (pinfunction "2_2") (pintype "passive"))
      (node (ref "C48") (pin "2") (pinfunction "2_2") (pintype "passive"))
      (node (ref "C49") (pin "2") (pinfunction "2_2") (pintype "passive"))
      (node (ref "C50") (pin "2") (pinfunction "2_2") (pintype "passive"))
      (node (ref "C51") (pin "2") (pinfunction "2_2") (pintype "passive"))
      (node (ref "C52") (pin "2") (pinfunction "2_2") (pintype "passive"))
      (node (ref "C53") (pin "2") (pinfunction "2_2") (pintype "passive"))
      (node (ref "C54") (pin "2") (pinfunction "2_2") (pintype "passive"))
      (node (ref "C55") (pin "2") (pinfunction "2_2") (pintype "passive"))
      (node (ref "C56") (pin "2") (pinfunction "2_2") (pintype "passive"))
      (node (ref "C57") (pin "2") (pinfunction "2_2") (pintype "passive"))
      (node (ref "C58") (pin "2") (pinfunction "2_2") (pintype "passive"))
      (node (ref "C59") (pin "2") (pinfunction "2_2") (pintype "passive"))
      (node (ref "C60") (pin "2") (pinfunction "2_2") (pintype "passive"))
      (node (ref "C61") (pin "2") (pinfunction "2_2") (pintype "passive"))
      (node (ref "C62") (pin "2") (pinfunction "2_2") (pintype "passive"))
      (node (ref "C63") (pin "2") (pinfunction "2_2") (pintype "passive"))
      (node (ref "C64") (pin "2") (pinfunction "2_2") (pintype "passive"))
      (node (ref "L3") (pin "2") (pinfunction "2_2") (pintype "passive"))
    )
    (net (code "14") (name "P3V3_DIOT") (class "Default")
      (node (ref "C2") (pin "2") (pinfunction "2_2") (pintype "passive"))
      (node (ref "C3") (pin "2") (pinfunction "2_2") (pintype "passive"))
      (node (ref "C35") (pin "2") (pinfunction "2_2") (pintype "passive"))
      (node (ref "C36") (pin "2") (pinfunction "2_2") (pintype "passive"))
      (node (ref "C4") (pin "2") (pinfunction "2_2") (pintype "passive"))
      (node (ref "C7") (pin "2") (pinfunction "2_2") (pintype "passive"))
      (node (ref "C9") (pin "2") (pinfunction "2_2") (pintype "passive"))
      (node (ref "IC1") (pin "5") (pinfunction "OUT_5") (pintype "power_in"))
    )
    (net (code "15") (name "P12V0") (class "Default")
      (node (ref "C18") (pin "1") (pinfunction "1_1") (pintype "passive"))
      (node (ref "C19") (pin "2") (pinfunction "2_2") (pintype "passive"))
      (node (ref "C20") (pin "2") (pinfunction "2_2") (pintype "passive"))
      (node (ref "C21") (pin "2") (pinfunction "2_2") (pintype "passive"))
      (node (ref "C22") (pin "2") (pinfunction "2_2") (pintype "passive"))
      (node (ref "C23") (pin "2") (pinfunction "2_2") (pintype "passive"))
      (node (ref "C24") (pin "2") (pinfunction "2_2") (pintype "passive"))
      (node (ref "IC5") (pin "6") (pinfunction "VIN_6") (pintype "input"))
      (node (ref "L1") (pin "2") (pinfunction "2_2") (pintype "passive"))
      (node (ref "R80") (pin "2") (pinfunction "2_2") (pintype "passive"))
    )
    (net (code "16") (name "unconnected-(IC1-BYP-Pad4)") (class "Default")
      (node (ref "IC1") (pin "4") (pinfunction "BYP_4") (pintype "passive+no_connect"))
    )
    (net (code "17") (name "unconnected-(IC5-PG-Pad5)") (class "Default")
      (node (ref "IC5") (pin "5") (pinfunction "PG_5") (pintype "output"))
    )
  )
)
